# Battery-Board.net
KiCad netlist of a schematic drawn in EAGLE
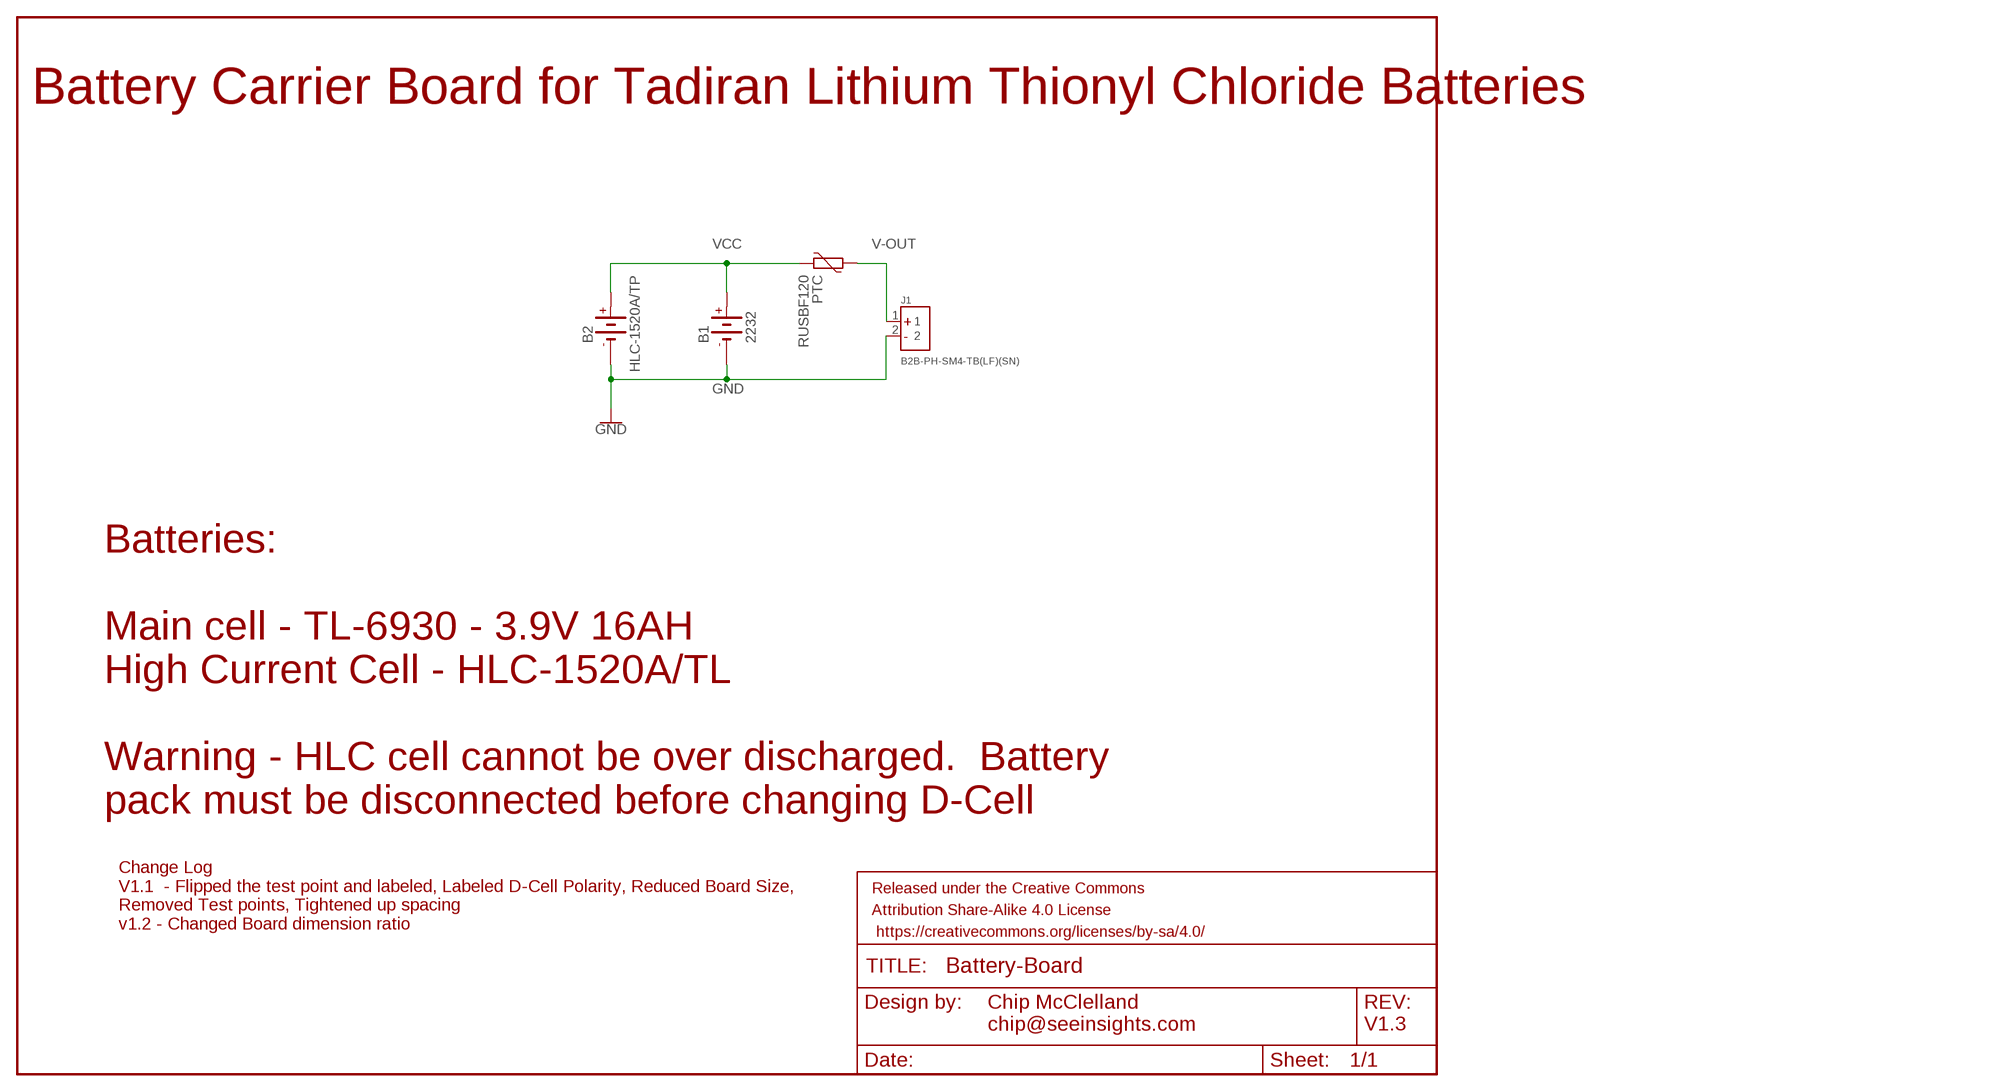
[diagram p0: schematic, sheet 1]

(export (version "E")
  (design (tool "Eeschema 10.0.6"))
  (components
    (comp (ref "B1")
      (value "2232")
      (footprint "eagle-import:2232")
      (fields (field (name "MF") "Keystone") (field (name "MP") "2226"))
      (libsource (lib "eagle-import") (part "2232"))
    )
    (comp (ref "B2")
      (value "HLC-1520A/TP")
      (footprint "eagle-import:HLC-1520A_TP")
      (fields (field (name "MFG") "Tadiran"))
      (libsource (lib "eagle-import") (part "HLC-1520A/TP"))
    )
    (comp (ref "FRAME1")
      (value "FRAME-LETTER")
      (footprint "eagle-import:CREATIVE_COMMONS")
      (libsource (lib "eagle-import") (part "FRAME-LETTER"))
    )
    (comp (ref "J1")
      (value "B2B-PH-SM4-TB(LF)(SN)")
      (footprint "eagle-import:JST_B2B-PH-SM4-TB(LF)(SN)")
      (fields (field (name "DIGI-KEY_PART_NUMBER") "455-1734-1-ND") (field (name "MF") "JST Sales"))
      (libsource (lib "eagle-import") (part "B2B-PH-SM4-TB(LF)(SN)"))
    )
    (comp (ref "PTC")
      (value "RUSBF120")
      (footprint "eagle-import:PTC-RUSBF120")
      (libsource (lib "eagle-import") (part "RUSBF120"))
    )
  )
  (nets
    (net (code "1") (name "/V-OUT") (class "Default")
      (node (ref "J1") (pin "1") (pinfunction "1_1") (pintype "passive"))
      (node (ref "PTC") (pin "2") (pinfunction "2_2") (pintype "passive"))
    )
    (net (code "2") (name "/VCC") (class "Default")
      (node (ref "B1") (pin "+") (pinfunction "+_+") (pintype "passive"))
      (node (ref "B2") (pin "+") (pinfunction "+_+") (pintype "passive"))
      (node (ref "PTC") (pin "1") (pinfunction "1_1") (pintype "passive"))
    )
    (net (code "3") (name "GND") (class "Default")
      (node (ref "B1") (pin "-") (pinfunction "-_-") (pintype "passive"))
      (node (ref "B2") (pin "-") (pinfunction "-_-") (pintype "passive"))
      (node (ref "B2") (pin "--") (pinfunction "-_--") (pintype "passive"))
      (node (ref "J1") (pin "2") (pinfunction "2_2") (pintype "passive"))
    )
  )
)
